# board.net
KiCad netlist of a schematic drawn in EAGLE
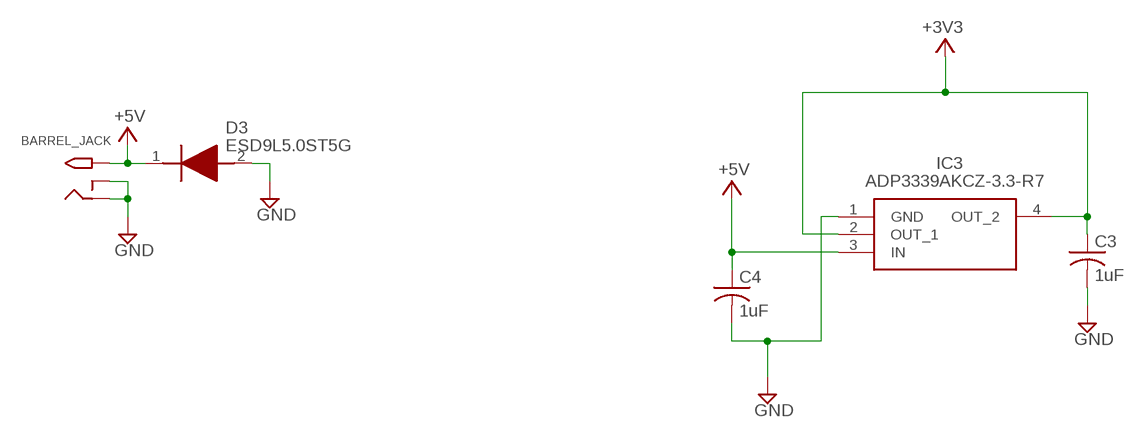
[diagram p0: schematic, sheet 1]
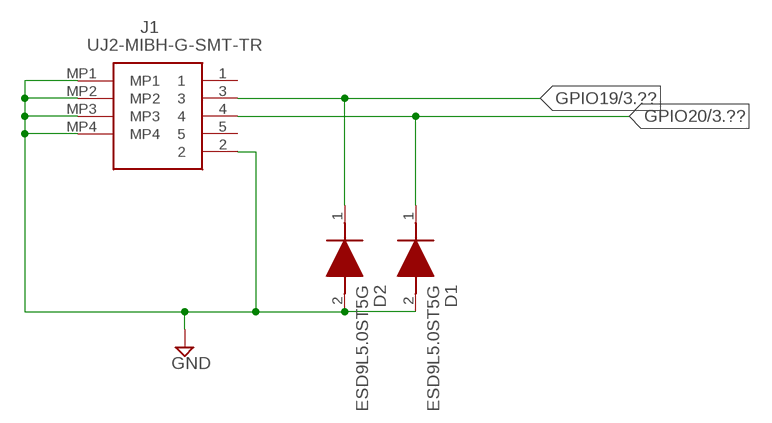
[diagram p1: schematic, sheet 2]
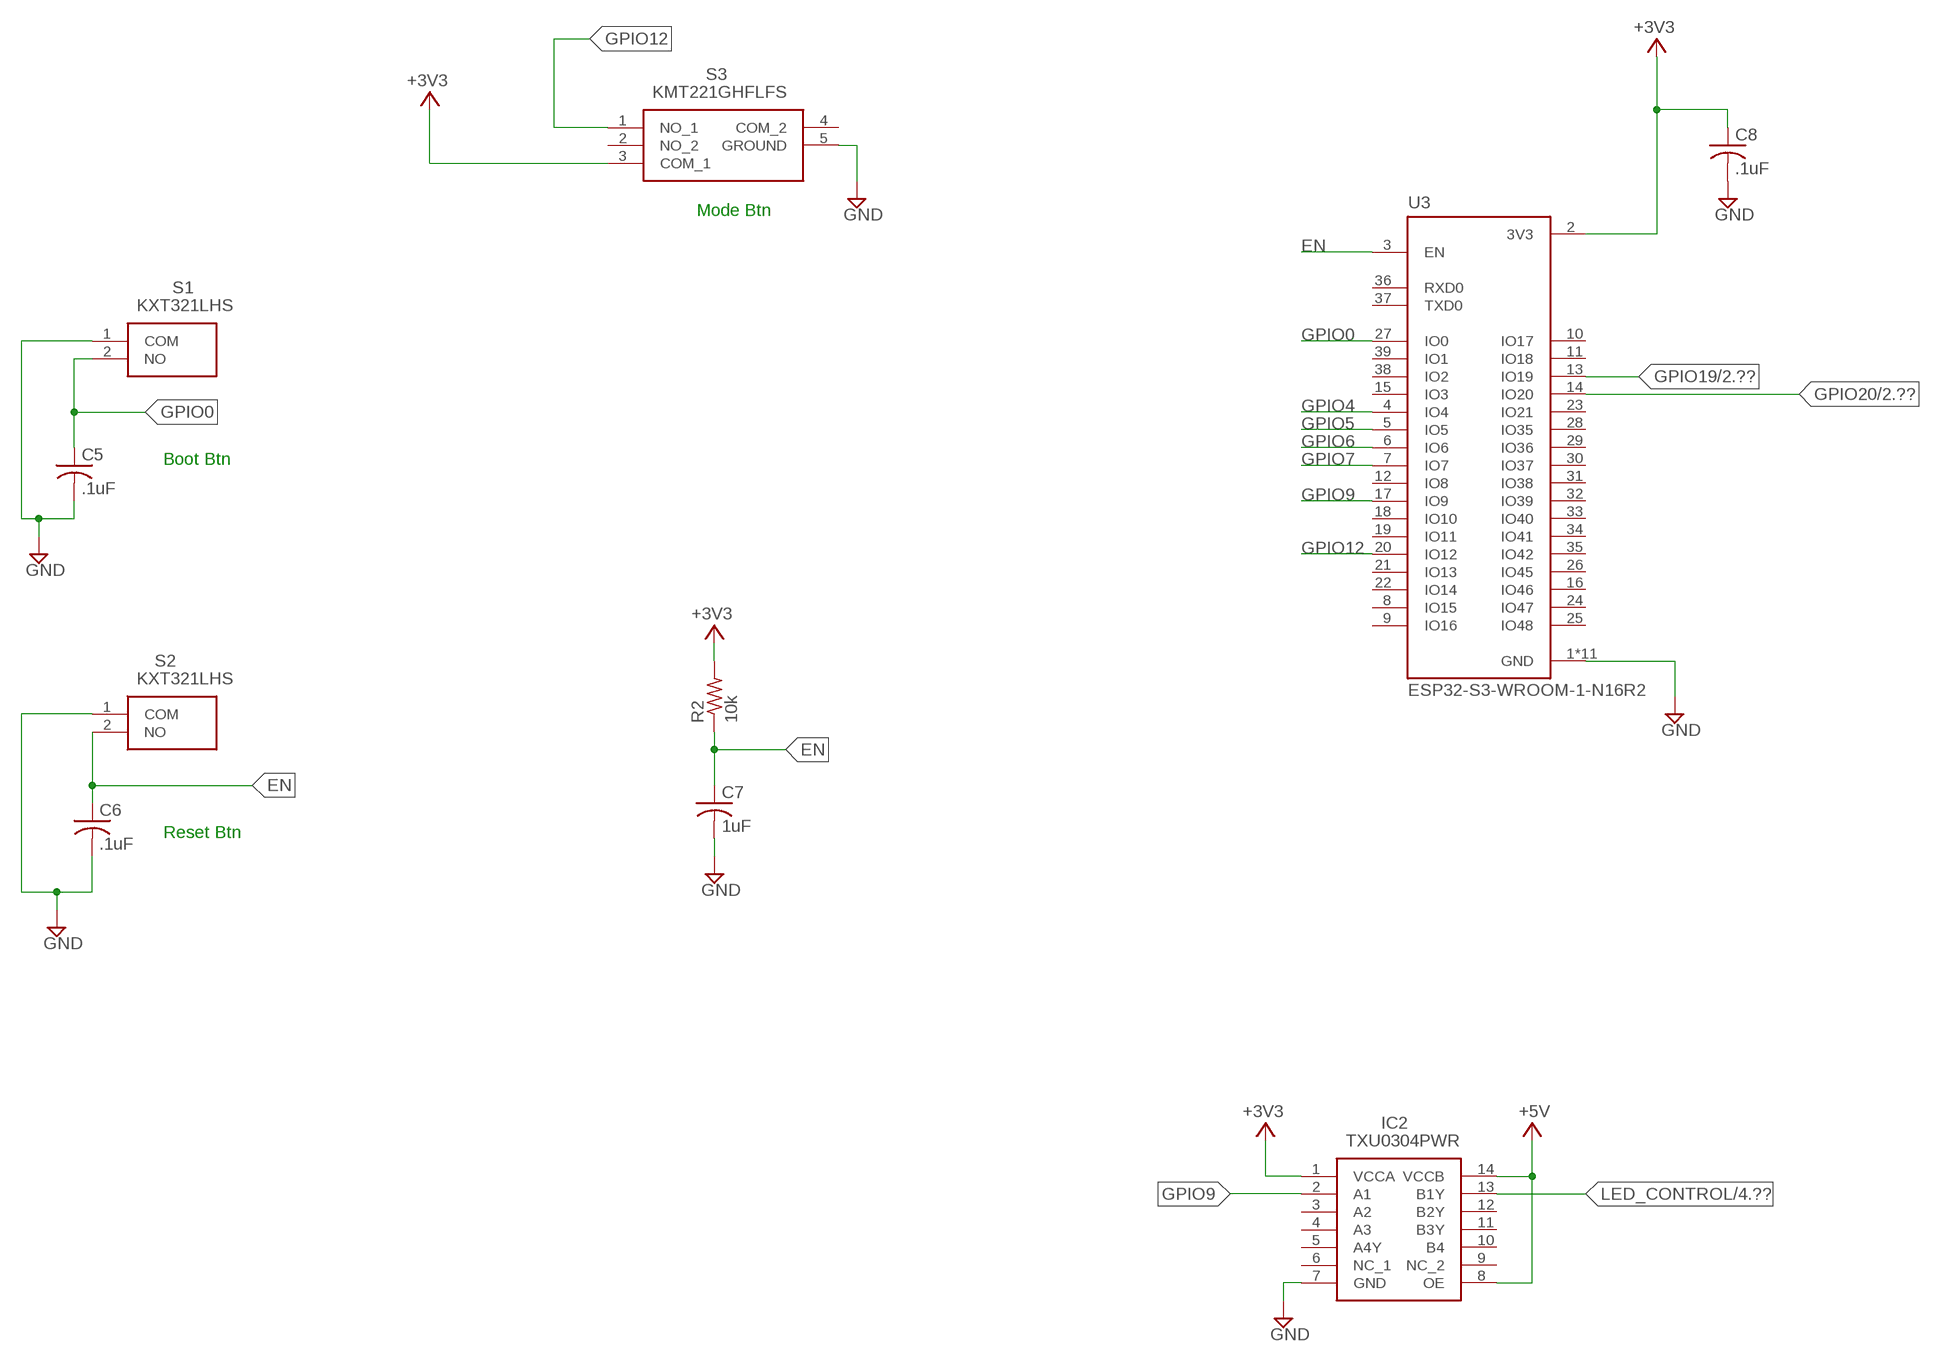
[diagram p2: schematic, sheet 3]
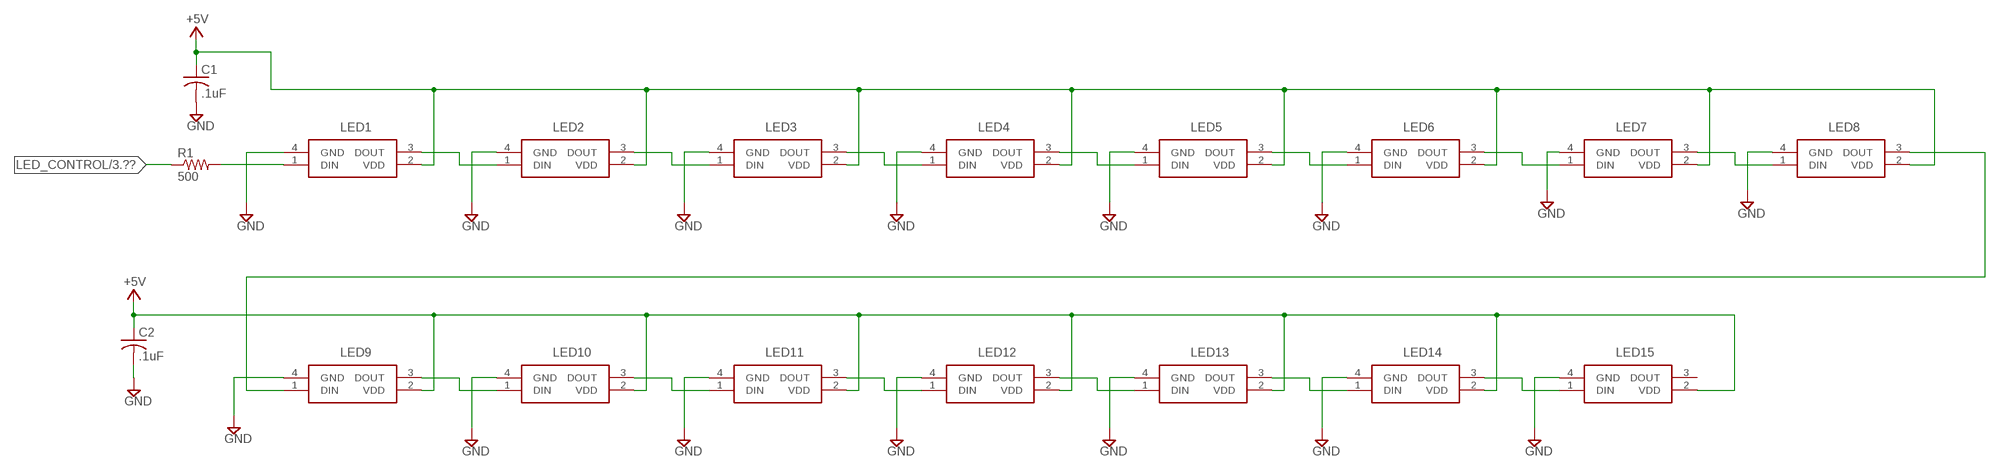
[diagram p3: schematic, sheet 4]
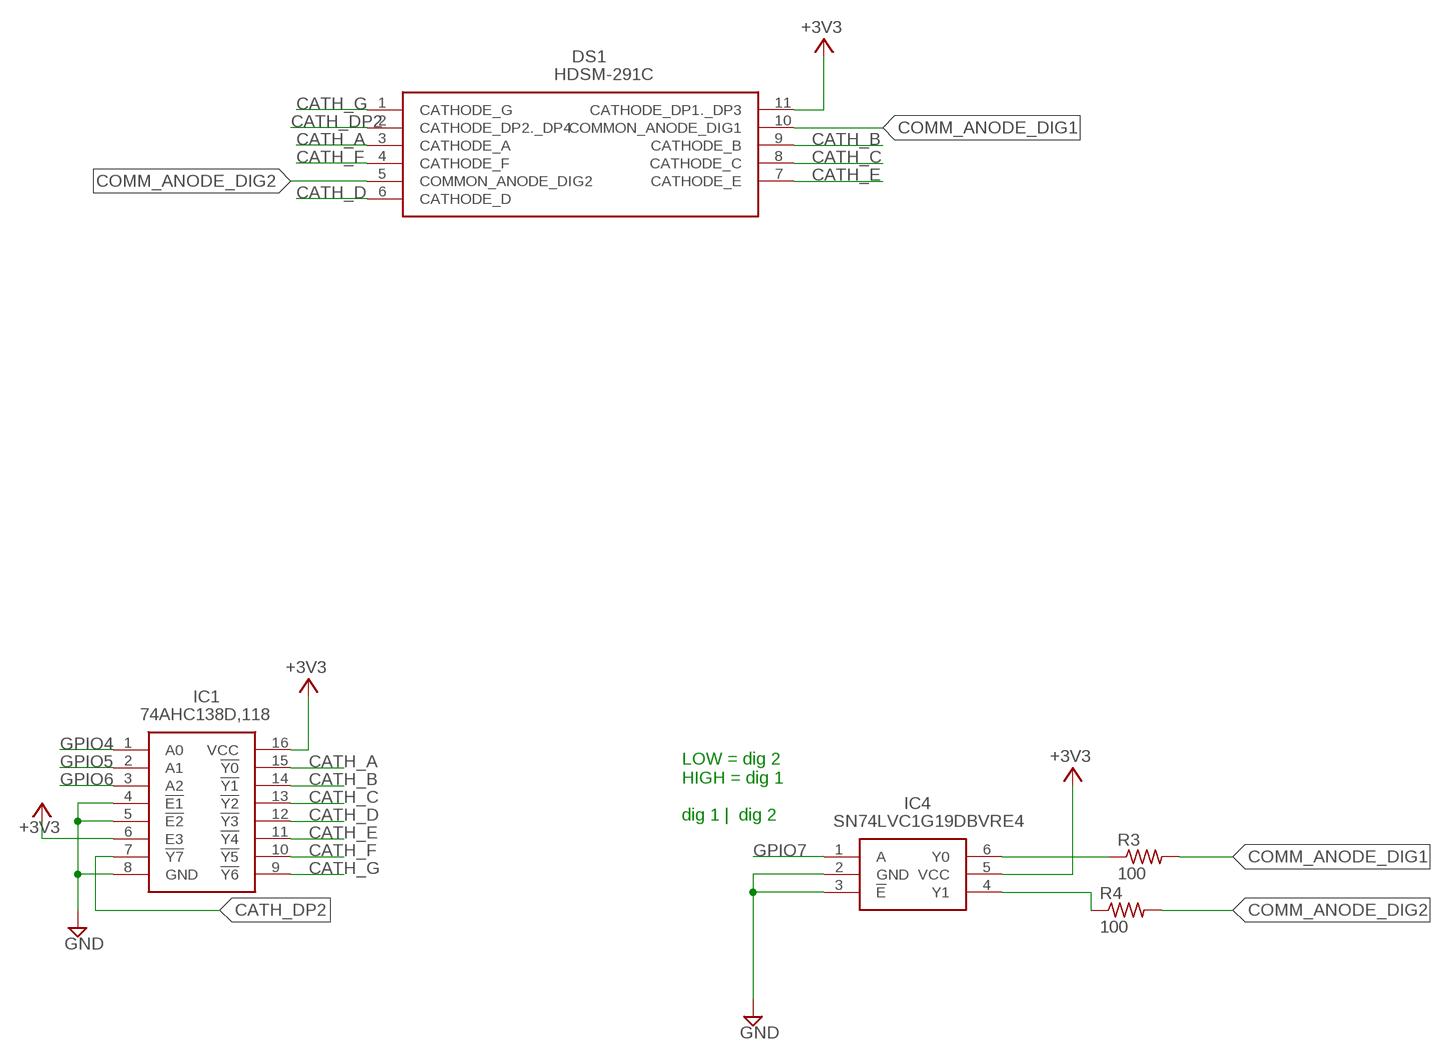
[diagram p4: schematic, sheet 5]

(export (version "E")
  (design (tool "Eeschema 10.0.6"))
  (components
    (comp (ref "C5")
      (value ".1uF")
      (footprint "eagle-import:C0402")
      (libsource (lib "eagle-import") (part "C-USC0402"))
    )
    (comp (ref "C6")
      (value ".1uF")
      (footprint "eagle-import:C0402")
      (libsource (lib "eagle-import") (part "C-USC0402"))
    )
    (comp (ref "C7")
      (value "1uF")
      (footprint "eagle-import:C0402")
      (libsource (lib "eagle-import") (part "C-USC0402"))
    )
    (comp (ref "C8")
      (value ".1uF")
      (footprint "eagle-import:C0402")
      (libsource (lib "eagle-import") (part "C-USC0402"))
    )
    (comp (ref "IC2")
      (value "TXU0304PWR")
      (footprint "eagle-import:SOP65P640X120-14N")
      (fields (field (name "MOUSER_PART_NUMBER") "595-TXU0304PWR"))
      (libsource (lib "eagle-import") (part "TXU0304PWR"))
    )
    (comp (ref "R2")
      (value "10k")
      (footprint "eagle-import:R0402")
      (libsource (lib "eagle-import") (part "R-US_R0402"))
    )
    (comp (ref "S1")
      (value "KXT321LHS")
      (footprint "eagle-import:KXT321LHS")
      (fields (field (name "MOUSER_PART_NUMBER") "611-KXT321LHS"))
      (libsource (lib "eagle-import") (part "KXT321LHS"))
    )
    (comp (ref "S2")
      (value "KXT321LHS")
      (footprint "eagle-import:KXT321LHS")
      (fields (field (name "MOUSER_PART_NUMBER") "611-KXT321LHS"))
      (libsource (lib "eagle-import") (part "KXT321LHS"))
    )
    (comp (ref "S3")
      (value "KMT221GHFLFS")
      (footprint "eagle-import:KMT221GHFLFS")
      (fields (field (name "MOUSER_PART_NUMBER") "611-KMT221GHFLFS"))
      (libsource (lib "eagle-import") (part "KMT221GHFLFS"))
    )
    (comp (ref "U3")
      (value "ESP32-S3-WROOM-1-N16R2")
      (footprint "eagle-import:XCVR_ESP32-S3-WROOM-1-N16R2")
      (fields (field (name "MF") "Espressif Systems"))
      (libsource (lib "eagle-import") (part "ESP32-S3-WROOM-1-N16R2"))
    )
    (comp (ref "D1")
      (value "ESD9L5.0ST5G")
      (footprint "eagle-import:SODFL1006X40N")
      (fields (field (name "MOUSER_PART_NUMBER") "863-ESD9L5.0ST5G"))
      (libsource (lib "eagle-import") (part "ESD9L5.0ST5G"))
    )
    (comp (ref "D2")
      (value "ESD9L5.0ST5G")
      (footprint "eagle-import:SODFL1006X40N")
      (fields (field (name "MOUSER_PART_NUMBER") "863-ESD9L5.0ST5G"))
      (libsource (lib "eagle-import") (part "ESD9L5.0ST5G"))
    )
    (comp (ref "J1")
      (value "UJ2-MIBH-G-SMT-TR")
      (footprint "eagle-import:UJ2MIBHGSMTTR")
      (fields (field (name "MOUSER_PART_NUMBER") "490-UJ2-MIBH-G-SMTTR"))
      (libsource (lib "eagle-import") (part "UJ2-MIBH-G-SMT-TR"))
    )
    (comp (ref "DS1")
      (value "HDSM-291C")
      (footprint "eagle-import:HDSM291C")
      (fields (field (name "MOUSER_PART_NUMBER") "630-HDSM-291C"))
      (libsource (lib "eagle-import") (part "HDSM-291C"))
    )
    (comp (ref "IC1")
      (value "74AHC138D,118")
      (footprint "eagle-import:SOIC127P600X175-16N")
      (fields (field (name "MOUSER_PART_NUMBER") "771-74AHC138D-T"))
      (libsource (lib "eagle-import") (part "74AHC138D,118"))
    )
    (comp (ref "IC4")
      (value "SN74LVC1G19DBVRE4")
      (footprint "eagle-import:SOT95P280X145-6N")
      (fields (field (name "MOUSER_PART_NUMBER") "595-74LVC1G19DBVRE4"))
      (libsource (lib "eagle-import") (part "SN74LVC1G19DBVRE4"))
    )
    (comp (ref "R3")
      (value "100")
      (footprint "eagle-import:R0402")
      (libsource (lib "eagle-import") (part "R-US_R0402"))
    )
    (comp (ref "R4")
      (value "100")
      (footprint "eagle-import:R0402")
      (libsource (lib "eagle-import") (part "R-US_R0402"))
    )
    (comp (ref "BARREL_JACK")
      (value "2.1MMJACKTHM")
      (footprint "eagle-import:PJ-102A")
      (libsource (lib "eagle-import") (part "2.1MMJACKTHM"))
    )
    (comp (ref "C3")
      (value "1uF")
      (footprint "eagle-import:C0402")
      (libsource (lib "eagle-import") (part "C-USC0402"))
    )
    (comp (ref "C4")
      (value "1uF")
      (footprint "eagle-import:C0402")
      (libsource (lib "eagle-import") (part "C-USC0402"))
    )
    (comp (ref "D3")
      (value "ESD9L5.0ST5G")
      (footprint "eagle-import:SODFL1006X40N")
      (fields (field (name "MOUSER_PART_NUMBER") "863-ESD9L5.0ST5G"))
      (libsource (lib "eagle-import") (part "ESD9L5.0ST5G"))
    )
    (comp (ref "IC3")
      (value "ADP3339AKCZ-3.3-R7")
      (footprint "eagle-import:SOT230P700X180-4N")
      (fields (field (name "MOUSER_PART_NUMBER") "584-ADP3339AKCZ3.3R7"))
      (libsource (lib "eagle-import") (part "ADP3339AKCZ-3.3-R7"))
    )
    (comp (ref "C1")
      (value ".1uF")
      (footprint "eagle-import:C0402")
      (libsource (lib "eagle-import") (part "C-USC0402"))
    )
    (comp (ref "C2")
      (value ".1uF")
      (footprint "eagle-import:C0402")
      (libsource (lib "eagle-import") (part "C-USC0402"))
    )
    (comp (ref "LED1")
      (value "4492__SK6805-EC_15_")
      (footprint "eagle-import:4492SK6805EC15")
      (fields (field (name "MANUFACTURER_PART_NUMBER") "4492 (SK6805-EC 15)"))
      (libsource (lib "eagle-import") (part "4492__SK6805-EC_15_"))
    )
    (comp (ref "LED2")
      (value "4492__SK6805-EC_15_")
      (footprint "eagle-import:4492SK6805EC15")
      (fields (field (name "MANUFACTURER_PART_NUMBER") "4492 (SK6805-EC 15)"))
      (libsource (lib "eagle-import") (part "4492__SK6805-EC_15_"))
    )
    (comp (ref "LED3")
      (value "4492__SK6805-EC_15_")
      (footprint "eagle-import:4492SK6805EC15")
      (fields (field (name "MANUFACTURER_PART_NUMBER") "4492 (SK6805-EC 15)"))
      (libsource (lib "eagle-import") (part "4492__SK6805-EC_15_"))
    )
    (comp (ref "LED4")
      (value "4492__SK6805-EC_15_")
      (footprint "eagle-import:4492SK6805EC15")
      (fields (field (name "MANUFACTURER_PART_NUMBER") "4492 (SK6805-EC 15)"))
      (libsource (lib "eagle-import") (part "4492__SK6805-EC_15_"))
    )
    (comp (ref "LED5")
      (value "4492__SK6805-EC_15_")
      (footprint "eagle-import:4492SK6805EC15")
      (fields (field (name "MANUFACTURER_PART_NUMBER") "4492 (SK6805-EC 15)"))
      (libsource (lib "eagle-import") (part "4492__SK6805-EC_15_"))
    )
    (comp (ref "LED6")
      (value "4492__SK6805-EC_15_")
      (footprint "eagle-import:4492SK6805EC15")
      (fields (field (name "MANUFACTURER_PART_NUMBER") "4492 (SK6805-EC 15)"))
      (libsource (lib "eagle-import") (part "4492__SK6805-EC_15_"))
    )
    (comp (ref "LED7")
      (value "4492__SK6805-EC_15_")
      (footprint "eagle-import:4492SK6805EC15")
      (fields (field (name "MANUFACTURER_PART_NUMBER") "4492 (SK6805-EC 15)"))
      (libsource (lib "eagle-import") (part "4492__SK6805-EC_15_"))
    )
    (comp (ref "LED8")
      (value "4492__SK6805-EC_15_")
      (footprint "eagle-import:4492SK6805EC15")
      (fields (field (name "MANUFACTURER_PART_NUMBER") "4492 (SK6805-EC 15)"))
      (libsource (lib "eagle-import") (part "4492__SK6805-EC_15_"))
    )
    (comp (ref "LED9")
      (value "4492__SK6805-EC_15_")
      (footprint "eagle-import:4492SK6805EC15")
      (fields (field (name "MANUFACTURER_PART_NUMBER") "4492 (SK6805-EC 15)"))
      (libsource (lib "eagle-import") (part "4492__SK6805-EC_15_"))
    )
    (comp (ref "LED10")
      (value "4492__SK6805-EC_15_")
      (footprint "eagle-import:4492SK6805EC15")
      (fields (field (name "MANUFACTURER_PART_NUMBER") "4492 (SK6805-EC 15)"))
      (libsource (lib "eagle-import") (part "4492__SK6805-EC_15_"))
    )
    (comp (ref "LED11")
      (value "4492__SK6805-EC_15_")
      (footprint "eagle-import:4492SK6805EC15")
      (fields (field (name "MANUFACTURER_PART_NUMBER") "4492 (SK6805-EC 15)"))
      (libsource (lib "eagle-import") (part "4492__SK6805-EC_15_"))
    )
    (comp (ref "LED12")
      (value "4492__SK6805-EC_15_")
      (footprint "eagle-import:4492SK6805EC15")
      (fields (field (name "MANUFACTURER_PART_NUMBER") "4492 (SK6805-EC 15)"))
      (libsource (lib "eagle-import") (part "4492__SK6805-EC_15_"))
    )
    (comp (ref "LED13")
      (value "4492__SK6805-EC_15_")
      (footprint "eagle-import:4492SK6805EC15")
      (fields (field (name "MANUFACTURER_PART_NUMBER") "4492 (SK6805-EC 15)"))
      (libsource (lib "eagle-import") (part "4492__SK6805-EC_15_"))
    )
    (comp (ref "LED14")
      (value "4492__SK6805-EC_15_")
      (footprint "eagle-import:4492SK6805EC15")
      (fields (field (name "MANUFACTURER_PART_NUMBER") "4492 (SK6805-EC 15)"))
      (libsource (lib "eagle-import") (part "4492__SK6805-EC_15_"))
    )
    (comp (ref "LED15")
      (value "4492__SK6805-EC_15_")
      (footprint "eagle-import:4492SK6805EC15")
      (fields (field (name "MANUFACTURER_PART_NUMBER") "4492 (SK6805-EC 15)"))
      (libsource (lib "eagle-import") (part "4492__SK6805-EC_15_"))
    )
    (comp (ref "R1")
      (value "500")
      (footprint "eagle-import:R0402")
      (libsource (lib "eagle-import") (part "R-US_R0402"))
    )
  )
  (nets
    (net (code "1") (name "+3V3") (class "Default")
      (node (ref "C3") (pin "1") (pinfunction "1_1") (pintype "passive"))
      (node (ref "C8") (pin "1") (pinfunction "1_1") (pintype "passive"))
      (node (ref "DS1") (pin "11") (pinfunction "CATHODE_DP1._DP3_11") (pintype "bidirectional"))
      (node (ref "IC1") (pin "16") (pinfunction "VCC_16") (pintype "bidirectional"))
      (node (ref "IC1") (pin "6") (pinfunction "E3_6") (pintype "bidirectional"))
      (node (ref "IC2") (pin "1") (pinfunction "VCCA_1") (pintype "bidirectional"))
      (node (ref "IC3") (pin "2") (pinfunction "OUT_1_2") (pintype "bidirectional"))
      (node (ref "IC3") (pin "4") (pinfunction "OUT_2_4") (pintype "bidirectional"))
      (node (ref "IC4") (pin "5") (pinfunction "VCC_5") (pintype "bidirectional"))
      (node (ref "R2") (pin "2") (pinfunction "2_2") (pintype "passive"))
      (node (ref "S3") (pin "3") (pinfunction "COM_1_3") (pintype "bidirectional"))
      (node (ref "U3") (pin "2") (pinfunction "3V3_2") (pintype "power_in"))
    )
    (net (code "2") (name "+5V") (class "Default")
      (node (ref "BARREL_JACK") (pin "TIP") (pinfunction "TIP_TIP") (pintype "bidirectional"))
      (node (ref "C1") (pin "1") (pinfunction "1_1") (pintype "passive"))
      (node (ref "C2") (pin "1") (pinfunction "1_1") (pintype "passive"))
      (node (ref "C4") (pin "1") (pinfunction "1_1") (pintype "passive"))
      (node (ref "D3") (pin "1") (pinfunction "K_1") (pintype "bidirectional"))
      (node (ref "IC2") (pin "14") (pinfunction "VCCB_14") (pintype "bidirectional"))
      (node (ref "IC2") (pin "8") (pinfunction "OE_8") (pintype "bidirectional"))
      (node (ref "IC3") (pin "3") (pinfunction "IN_3") (pintype "bidirectional"))
      (node (ref "LED1") (pin "2") (pinfunction "VDD_2") (pintype "bidirectional"))
      (node (ref "LED10") (pin "2") (pinfunction "VDD_2") (pintype "bidirectional"))
      (node (ref "LED11") (pin "2") (pinfunction "VDD_2") (pintype "bidirectional"))
      (node (ref "LED12") (pin "2") (pinfunction "VDD_2") (pintype "bidirectional"))
      (node (ref "LED13") (pin "2") (pinfunction "VDD_2") (pintype "bidirectional"))
      (node (ref "LED14") (pin "2") (pinfunction "VDD_2") (pintype "bidirectional"))
      (node (ref "LED15") (pin "2") (pinfunction "VDD_2") (pintype "bidirectional"))
      (node (ref "LED2") (pin "2") (pinfunction "VDD_2") (pintype "bidirectional"))
      (node (ref "LED3") (pin "2") (pinfunction "VDD_2") (pintype "bidirectional"))
      (node (ref "LED4") (pin "2") (pinfunction "VDD_2") (pintype "bidirectional"))
      (node (ref "LED5") (pin "2") (pinfunction "VDD_2") (pintype "bidirectional"))
      (node (ref "LED6") (pin "2") (pinfunction "VDD_2") (pintype "bidirectional"))
      (node (ref "LED7") (pin "2") (pinfunction "VDD_2") (pintype "bidirectional"))
      (node (ref "LED8") (pin "2") (pinfunction "VDD_2") (pintype "bidirectional"))
      (node (ref "LED9") (pin "2") (pinfunction "VDD_2") (pintype "bidirectional"))
    )
    (net (code "3") (name "CATH_A") (class "Default")
      (node (ref "DS1") (pin "3") (pinfunction "CATHODE_A_3") (pintype "bidirectional"))
      (node (ref "IC1") (pin "15") (pinfunction "~{Y0}_15") (pintype "bidirectional"))
    )
    (net (code "4") (name "CATH_B") (class "Default")
      (node (ref "DS1") (pin "9") (pinfunction "CATHODE_B_9") (pintype "bidirectional"))
      (node (ref "IC1") (pin "14") (pinfunction "~{Y1}_14") (pintype "bidirectional"))
    )
    (net (code "5") (name "CATH_C") (class "Default")
      (node (ref "DS1") (pin "8") (pinfunction "CATHODE_C_8") (pintype "bidirectional"))
      (node (ref "IC1") (pin "13") (pinfunction "~{Y2}_13") (pintype "bidirectional"))
    )
    (net (code "6") (name "CATH_D") (class "Default")
      (node (ref "DS1") (pin "6") (pinfunction "CATHODE_D_6") (pintype "bidirectional"))
      (node (ref "IC1") (pin "12") (pinfunction "~{Y3}_12") (pintype "bidirectional"))
    )
    (net (code "7") (name "CATH_DP2") (class "Default")
      (node (ref "DS1") (pin "2") (pinfunction "CATHODE_DP2._DP4_2") (pintype "bidirectional"))
      (node (ref "IC1") (pin "7") (pinfunction "~{Y7}_7") (pintype "bidirectional"))
    )
    (net (code "8") (name "CATH_E") (class "Default")
      (node (ref "DS1") (pin "7") (pinfunction "CATHODE_E_7") (pintype "bidirectional"))
      (node (ref "IC1") (pin "11") (pinfunction "~{Y4}_11") (pintype "bidirectional"))
    )
    (net (code "9") (name "CATH_F") (class "Default")
      (node (ref "DS1") (pin "4") (pinfunction "CATHODE_F_4") (pintype "bidirectional"))
      (node (ref "IC1") (pin "10") (pinfunction "~{Y5}_10") (pintype "bidirectional"))
    )
    (net (code "10") (name "CATH_G") (class "Default")
      (node (ref "DS1") (pin "1") (pinfunction "CATHODE_G_1") (pintype "bidirectional"))
      (node (ref "IC1") (pin "9") (pinfunction "~{Y6}_9") (pintype "bidirectional"))
    )
    (net (code "11") (name "COMM_ANODE_DIG1") (class "Default")
      (node (ref "DS1") (pin "10") (pinfunction "COMMON_ANODE_DIG1_10") (pintype "bidirectional"))
      (node (ref "R3") (pin "2") (pinfunction "2_2") (pintype "passive"))
    )
    (net (code "12") (name "COMM_ANODE_DIG2") (class "Default")
      (node (ref "DS1") (pin "5") (pinfunction "COMMON_ANODE_DIG2_5") (pintype "bidirectional"))
      (node (ref "R4") (pin "2") (pinfunction "2_2") (pintype "passive"))
    )
    (net (code "13") (name "EN") (class "Default")
      (node (ref "C6") (pin "1") (pinfunction "1_1") (pintype "passive"))
      (node (ref "C7") (pin "1") (pinfunction "1_1") (pintype "passive"))
      (node (ref "R2") (pin "1") (pinfunction "1_1") (pintype "passive"))
      (node (ref "S2") (pin "2") (pinfunction "NO_2") (pintype "bidirectional"))
      (node (ref "U3") (pin "3") (pinfunction "EN_3") (pintype "input"))
    )
    (net (code "14") (name "GND") (class "Default")
      (node (ref "BARREL_JACK") (pin "RING") (pinfunction "RING_RING") (pintype "bidirectional"))
      (node (ref "BARREL_JACK") (pin "RING_SW") (pinfunction "RING_SW_RING_SW") (pintype "bidirectional"))
      (node (ref "C1") (pin "2") (pinfunction "2_2") (pintype "passive"))
      (node (ref "C2") (pin "2") (pinfunction "2_2") (pintype "passive"))
      (node (ref "C3") (pin "2") (pinfunction "2_2") (pintype "passive"))
      (node (ref "C4") (pin "2") (pinfunction "2_2") (pintype "passive"))
      (node (ref "C5") (pin "2") (pinfunction "2_2") (pintype "passive"))
      (node (ref "C6") (pin "2") (pinfunction "2_2") (pintype "passive"))
      (node (ref "C7") (pin "2") (pinfunction "2_2") (pintype "passive"))
      (node (ref "C8") (pin "2") (pinfunction "2_2") (pintype "passive"))
      (node (ref "D1") (pin "2") (pinfunction "A_2") (pintype "bidirectional"))
      (node (ref "D2") (pin "2") (pinfunction "A_2") (pintype "bidirectional"))
      (node (ref "D3") (pin "2") (pinfunction "A_2") (pintype "bidirectional"))
      (node (ref "IC1") (pin "4") (pinfunction "~{E1}_4") (pintype "bidirectional"))
      (node (ref "IC1") (pin "5") (pinfunction "~{E2}_5") (pintype "bidirectional"))
      (node (ref "IC1") (pin "8") (pinfunction "GND_8") (pintype "bidirectional"))
      (node (ref "IC2") (pin "7") (pinfunction "GND_7") (pintype "bidirectional"))
      (node (ref "IC3") (pin "1") (pinfunction "GND_1") (pintype "bidirectional"))
      (node (ref "IC4") (pin "2") (pinfunction "GND_2") (pintype "bidirectional"))
      (node (ref "IC4") (pin "3") (pinfunction "~{E}_3") (pintype "bidirectional"))
      (node (ref "J1") (pin "2") (pinfunction "2_2") (pintype "bidirectional"))
      (node (ref "J1") (pin "MP1") (pinfunction "MP1_MP1") (pintype "bidirectional"))
      (node (ref "J1") (pin "MP2") (pinfunction "MP2_MP2") (pintype "bidirectional"))
      (node (ref "J1") (pin "MP3") (pinfunction "MP3_MP3") (pintype "bidirectional"))
      (node (ref "J1") (pin "MP4") (pinfunction "MP4_MP4") (pintype "bidirectional"))
      (node (ref "LED1") (pin "4") (pinfunction "GND_4") (pintype "bidirectional"))
      (node (ref "LED10") (pin "4") (pinfunction "GND_4") (pintype "bidirectional"))
      (node (ref "LED11") (pin "4") (pinfunction "GND_4") (pintype "bidirectional"))
      (node (ref "LED12") (pin "4") (pinfunction "GND_4") (pintype "bidirectional"))
      (node (ref "LED13") (pin "4") (pinfunction "GND_4") (pintype "bidirectional"))
      (node (ref "LED14") (pin "4") (pinfunction "GND_4") (pintype "bidirectional"))
      (node (ref "LED15") (pin "4") (pinfunction "GND_4") (pintype "bidirectional"))
      (node (ref "LED2") (pin "4") (pinfunction "GND_4") (pintype "bidirectional"))
      (node (ref "LED3") (pin "4") (pinfunction "GND_4") (pintype "bidirectional"))
      (node (ref "LED4") (pin "4") (pinfunction "GND_4") (pintype "bidirectional"))
      (node (ref "LED5") (pin "4") (pinfunction "GND_4") (pintype "bidirectional"))
      (node (ref "LED6") (pin "4") (pinfunction "GND_4") (pintype "bidirectional"))
      (node (ref "LED7") (pin "4") (pinfunction "GND_4") (pintype "bidirectional"))
      (node (ref "LED8") (pin "4") (pinfunction "GND_4") (pintype "bidirectional"))
      (node (ref "LED9") (pin "4") (pinfunction "GND_4") (pintype "bidirectional"))
      (node (ref "S1") (pin "1") (pinfunction "COM_1") (pintype "bidirectional"))
      (node (ref "S2") (pin "1") (pinfunction "COM_1") (pintype "bidirectional"))
      (node (ref "S3") (pin "5") (pinfunction "GROUND_5") (pintype "bidirectional"))
      (node (ref "U3") (pin "1") (pinfunction "GND_1") (pintype "power_in"))
      (node (ref "U3") (pin "40") (pinfunction "GND_40") (pintype "power_in"))
      (node (ref "U3") (pin "41_1") (pinfunction "GND_41_1") (pintype "power_in"))
      (node (ref "U3") (pin "41_2") (pinfunction "GND_41_2") (pintype "power_in"))
      (node (ref "U3") (pin "41_3") (pinfunction "GND_41_3") (pintype "power_in"))
      (node (ref "U3") (pin "41_4") (pinfunction "GND_41_4") (pintype "power_in"))
      (node (ref "U3") (pin "41_5") (pinfunction "GND_41_5") (pintype "power_in"))
      (node (ref "U3") (pin "41_6") (pinfunction "GND_41_6") (pintype "power_in"))
      (node (ref "U3") (pin "41_7") (pinfunction "GND_41_7") (pintype "power_in"))
      (node (ref "U3") (pin "41_8") (pinfunction "GND_41_8") (pintype "power_in"))
      (node (ref "U3") (pin "41_9") (pinfunction "GND_41_9") (pintype "power_in"))
    )
    (net (code "15") (name "GPIO0") (class "Default")
      (node (ref "C5") (pin "1") (pinfunction "1_1") (pintype "passive"))
      (node (ref "S1") (pin "2") (pinfunction "NO_2") (pintype "bidirectional"))
      (node (ref "U3") (pin "27") (pinfunction "IO0_27") (pintype "bidirectional"))
    )
    (net (code "16") (name "GPIO4") (class "Default")
      (node (ref "IC1") (pin "1") (pinfunction "A0_1") (pintype "bidirectional"))
      (node (ref "U3") (pin "4") (pinfunction "IO4_4") (pintype "bidirectional"))
    )
    (net (code "17") (name "GPIO5") (class "Default")
      (node (ref "IC1") (pin "2") (pinfunction "A1_2") (pintype "bidirectional"))
      (node (ref "U3") (pin "5") (pinfunction "IO5_5") (pintype "bidirectional"))
    )
    (net (code "18") (name "GPIO6") (class "Default")
      (node (ref "IC1") (pin "3") (pinfunction "A2_3") (pintype "bidirectional"))
      (node (ref "U3") (pin "6") (pinfunction "IO6_6") (pintype "bidirectional"))
    )
    (net (code "19") (name "GPIO7") (class "Default")
      (node (ref "IC4") (pin "1") (pinfunction "A_1") (pintype "bidirectional"))
      (node (ref "U3") (pin "7") (pinfunction "IO7_7") (pintype "bidirectional"))
    )
    (net (code "20") (name "GPIO9") (class "Default")
      (node (ref "IC2") (pin "2") (pinfunction "A1_2") (pintype "bidirectional"))
      (node (ref "U3") (pin "17") (pinfunction "IO9_17") (pintype "bidirectional"))
    )
    (net (code "21") (name "GPIO12") (class "Default")
      (node (ref "S3") (pin "1") (pinfunction "NO_1_1") (pintype "bidirectional"))
      (node (ref "U3") (pin "20") (pinfunction "IO12_20") (pintype "bidirectional"))
    )
    (net (code "22") (name "GPIO19") (class "Default")
      (node (ref "D2") (pin "1") (pinfunction "K_1") (pintype "bidirectional"))
      (node (ref "J1") (pin "3") (pinfunction "3_3") (pintype "bidirectional"))
      (node (ref "U3") (pin "13") (pinfunction "IO19_13") (pintype "bidirectional"))
    )
    (net (code "23") (name "GPIO20") (class "Default")
      (node (ref "D1") (pin "1") (pinfunction "K_1") (pintype "bidirectional"))
      (node (ref "J1") (pin "4") (pinfunction "4_4") (pintype "bidirectional"))
      (node (ref "U3") (pin "14") (pinfunction "IO20_14") (pintype "bidirectional"))
    )
    (net (code "24") (name "LED_CONTROL") (class "Default")
      (node (ref "IC2") (pin "13") (pinfunction "B1Y_13") (pintype "bidirectional"))
      (node (ref "R1") (pin "1") (pinfunction "1_1") (pintype "passive"))
    )
    (net (code "25") (name "Net-(IC4-Y0)") (class "Default")
      (node (ref "IC4") (pin "6") (pinfunction "Y0_6") (pintype "bidirectional"))
      (node (ref "R3") (pin "1") (pinfunction "1_1") (pintype "passive"))
    )
    (net (code "26") (name "Net-(IC4-Y1)") (class "Default")
      (node (ref "IC4") (pin "4") (pinfunction "Y1_4") (pintype "bidirectional"))
      (node (ref "R4") (pin "1") (pinfunction "1_1") (pintype "passive"))
    )
    (net (code "27") (name "Net-(LED1-DIN)") (class "Default")
      (node (ref "LED1") (pin "1") (pinfunction "DIN_1") (pintype "bidirectional"))
      (node (ref "R1") (pin "2") (pinfunction "2_2") (pintype "passive"))
    )
    (net (code "28") (name "Net-(LED1-DOUT)") (class "Default")
      (node (ref "LED1") (pin "3") (pinfunction "DOUT_3") (pintype "bidirectional"))
      (node (ref "LED2") (pin "1") (pinfunction "DIN_1") (pintype "bidirectional"))
    )
    (net (code "29") (name "Net-(LED2-DOUT)") (class "Default")
      (node (ref "LED2") (pin "3") (pinfunction "DOUT_3") (pintype "bidirectional"))
      (node (ref "LED3") (pin "1") (pinfunction "DIN_1") (pintype "bidirectional"))
    )
    (net (code "30") (name "Net-(LED3-DOUT)") (class "Default")
      (node (ref "LED3") (pin "3") (pinfunction "DOUT_3") (pintype "bidirectional"))
      (node (ref "LED4") (pin "1") (pinfunction "DIN_1") (pintype "bidirectional"))
    )
    (net (code "31") (name "Net-(LED4-DOUT)") (class "Default")
      (node (ref "LED4") (pin "3") (pinfunction "DOUT_3") (pintype "bidirectional"))
      (node (ref "LED5") (pin "1") (pinfunction "DIN_1") (pintype "bidirectional"))
    )
    (net (code "32") (name "Net-(LED5-DOUT)") (class "Default")
      (node (ref "LED5") (pin "3") (pinfunction "DOUT_3") (pintype "bidirectional"))
      (node (ref "LED6") (pin "1") (pinfunction "DIN_1") (pintype "bidirectional"))
    )
    (net (code "33") (name "Net-(LED6-DOUT)") (class "Default")
      (node (ref "LED6") (pin "3") (pinfunction "DOUT_3") (pintype "bidirectional"))
      (node (ref "LED7") (pin "1") (pinfunction "DIN_1") (pintype "bidirectional"))
    )
    (net (code "34") (name "Net-(LED7-DOUT)") (class "Default")
      (node (ref "LED7") (pin "3") (pinfunction "DOUT_3") (pintype "bidirectional"))
      (node (ref "LED8") (pin "1") (pinfunction "DIN_1") (pintype "bidirectional"))
    )
    (net (code "35") (name "Net-(LED8-DOUT)") (class "Default")
      (node (ref "LED8") (pin "3") (pinfunction "DOUT_3") (pintype "bidirectional"))
      (node (ref "LED9") (pin "1") (pinfunction "DIN_1") (pintype "bidirectional"))
    )
    (net (code "36") (name "Net-(LED10-DIN)") (class "Default")
      (node (ref "LED10") (pin "1") (pinfunction "DIN_1") (pintype "bidirectional"))
      (node (ref "LED9") (pin "3") (pinfunction "DOUT_3") (pintype "bidirectional"))
    )
    (net (code "37") (name "Net-(LED10-DOUT)") (class "Default")
      (node (ref "LED10") (pin "3") (pinfunction "DOUT_3") (pintype "bidirectional"))
      (node (ref "LED11") (pin "1") (pinfunction "DIN_1") (pintype "bidirectional"))
    )
    (net (code "38") (name "Net-(LED11-DOUT)") (class "Default")
      (node (ref "LED11") (pin "3") (pinfunction "DOUT_3") (pintype "bidirectional"))
      (node (ref "LED12") (pin "1") (pinfunction "DIN_1") (pintype "bidirectional"))
    )
    (net (code "39") (name "Net-(LED12-DOUT)") (class "Default")
      (node (ref "LED12") (pin "3") (pinfunction "DOUT_3") (pintype "bidirectional"))
      (node (ref "LED13") (pin "1") (pinfunction "DIN_1") (pintype "bidirectional"))
    )
    (net (code "40") (name "Net-(LED13-DOUT)") (class "Default")
      (node (ref "LED13") (pin "3") (pinfunction "DOUT_3") (pintype "bidirectional"))
      (node (ref "LED14") (pin "1") (pinfunction "DIN_1") (pintype "bidirectional"))
    )
    (net (code "41") (name "Net-(LED14-DOUT)") (class "Default")
      (node (ref "LED14") (pin "3") (pinfunction "DOUT_3") (pintype "bidirectional"))
      (node (ref "LED15") (pin "1") (pinfunction "DIN_1") (pintype "bidirectional"))
    )
    (net (code "42") (name "unconnected-(IC2-A2-Pad3)") (class "Default")
      (node (ref "IC2") (pin "3") (pinfunction "A2_3") (pintype "bidirectional"))
    )
    (net (code "43") (name "unconnected-(IC2-A3-Pad4)") (class "Default")
      (node (ref "IC2") (pin "4") (pinfunction "A3_4") (pintype "bidirectional"))
    )
    (net (code "44") (name "unconnected-(IC2-A4Y-Pad5)") (class "Default")
      (node (ref "IC2") (pin "5") (pinfunction "A4Y_5") (pintype "bidirectional"))
    )
    (net (code "45") (name "unconnected-(IC2-B2Y-Pad12)") (class "Default")
      (node (ref "IC2") (pin "12") (pinfunction "B2Y_12") (pintype "bidirectional"))
    )
    (net (code "46") (name "unconnected-(IC2-B3Y-Pad11)") (class "Default")
      (node (ref "IC2") (pin "11") (pinfunction "B3Y_11") (pintype "bidirectional"))
    )
    (net (code "47") (name "unconnected-(IC2-B4-Pad10)") (class "Default")
      (node (ref "IC2") (pin "10") (pinfunction "B4_10") (pintype "bidirectional"))
    )
    (net (code "48") (name "unconnected-(IC2-NC_1-Pad6)") (class "Default")
      (node (ref "IC2") (pin "6") (pinfunction "NC_1_6") (pintype "bidirectional"))
    )
    (net (code "49") (name "unconnected-(IC2-NC_2-Pad9)") (class "Default")
      (node (ref "IC2") (pin "9") (pinfunction "NC_2_9") (pintype "bidirectional"))
    )
    (net (code "50") (name "unconnected-(J1-Pad1)") (class "Default")
      (node (ref "J1") (pin "1") (pinfunction "1_1") (pintype "bidirectional"))
    )
    (net (code "51") (name "unconnected-(J1-Pad5)") (class "Default")
      (node (ref "J1") (pin "5") (pinfunction "5_5") (pintype "bidirectional"))
    )
    (net (code "52") (name "unconnected-(LED15-DOUT-Pad3)") (class "Default")
      (node (ref "LED15") (pin "3") (pinfunction "DOUT_3") (pintype "bidirectional"))
    )
    (net (code "53") (name "unconnected-(S3-COM_2-Pad4)") (class "Default")
      (node (ref "S3") (pin "4") (pinfunction "COM_2_4") (pintype "bidirectional"))
    )
    (net (code "54") (name "unconnected-(S3-NO_2-Pad2)") (class "Default")
      (node (ref "S3") (pin "2") (pinfunction "NO_2_2") (pintype "bidirectional"))
    )
    (net (code "55") (name "unconnected-(U3-IO1-Pad39)") (class "Default")
      (node (ref "U3") (pin "39") (pinfunction "IO1_39") (pintype "bidirectional"))
    )
    (net (code "56") (name "unconnected-(U3-IO2-Pad38)") (class "Default")
      (node (ref "U3") (pin "38") (pinfunction "IO2_38") (pintype "bidirectional"))
    )
    (net (code "57") (name "unconnected-(U3-IO3-Pad15)") (class "Default")
      (node (ref "U3") (pin "15") (pinfunction "IO3_15") (pintype "bidirectional"))
    )
    (net (code "58") (name "unconnected-(U3-IO8-Pad12)") (class "Default")
      (node (ref "U3") (pin "12") (pinfunction "IO8_12") (pintype "bidirectional"))
    )
    (net (code "59") (name "unconnected-(U3-IO10-Pad18)") (class "Default")
      (node (ref "U3") (pin "18") (pinfunction "IO10_18") (pintype "bidirectional"))
    )
    (net (code "60") (name "unconnected-(U3-IO11-Pad19)") (class "Default")
      (node (ref "U3") (pin "19") (pinfunction "IO11_19") (pintype "bidirectional"))
    )
    (net (code "61") (name "unconnected-(U3-IO13-Pad21)") (class "Default")
      (node (ref "U3") (pin "21") (pinfunction "IO13_21") (pintype "bidirectional"))
    )
    (net (code "62") (name "unconnected-(U3-IO14-Pad22)") (class "Default")
      (node (ref "U3") (pin "22") (pinfunction "IO14_22") (pintype "bidirectional"))
    )
    (net (code "63") (name "unconnected-(U3-IO15-Pad8)") (class "Default")
      (node (ref "U3") (pin "8") (pinfunction "IO15_8") (pintype "bidirectional"))
    )
    (net (code "64") (name "unconnected-(U3-IO16-Pad9)") (class "Default")
      (node (ref "U3") (pin "9") (pinfunction "IO16_9") (pintype "bidirectional"))
    )
    (net (code "65") (name "unconnected-(U3-IO17-Pad10)") (class "Default")
      (node (ref "U3") (pin "10") (pinfunction "IO17_10") (pintype "bidirectional"))
    )
    (net (code "66") (name "unconnected-(U3-IO18-Pad11)") (class "Default")
      (node (ref "U3") (pin "11") (pinfunction "IO18_11") (pintype "bidirectional"))
    )
    (net (code "67") (name "unconnected-(U3-IO21-Pad23)") (class "Default")
      (node (ref "U3") (pin "23") (pinfunction "IO21_23") (pintype "bidirectional"))
    )
    (net (code "68") (name "unconnected-(U3-IO35-Pad28)") (class "Default")
      (node (ref "U3") (pin "28") (pinfunction "IO35_28") (pintype "bidirectional"))
    )
    (net (code "69") (name "unconnected-(U3-IO36-Pad29)") (class "Default")
      (node (ref "U3") (pin "29") (pinfunction "IO36_29") (pintype "bidirectional"))
    )
    (net (code "70") (name "unconnected-(U3-IO37-Pad30)") (class "Default")
      (node (ref "U3") (pin "30") (pinfunction "IO37_30") (pintype "bidirectional"))
    )
    (net (code "71") (name "unconnected-(U3-IO38-Pad31)") (class "Default")
      (node (ref "U3") (pin "31") (pinfunction "IO38_31") (pintype "bidirectional"))
    )
    (net (code "72") (name "unconnected-(U3-IO39-Pad32)") (class "Default")
      (node (ref "U3") (pin "32") (pinfunction "IO39_32") (pintype "bidirectional"))
    )
    (net (code "73") (name "unconnected-(U3-IO40-Pad33)") (class "Default")
      (node (ref "U3") (pin "33") (pinfunction "IO40_33") (pintype "bidirectional"))
    )
    (net (code "74") (name "unconnected-(U3-IO41-Pad34)") (class "Default")
      (node (ref "U3") (pin "34") (pinfunction "IO41_34") (pintype "bidirectional"))
    )
    (net (code "75") (name "unconnected-(U3-IO42-Pad35)") (class "Default")
      (node (ref "U3") (pin "35") (pinfunction "IO42_35") (pintype "bidirectional"))
    )
    (net (code "76") (name "unconnected-(U3-IO45-Pad26)") (class "Default")
      (node (ref "U3") (pin "26") (pinfunction "IO45_26") (pintype "bidirectional"))
    )
    (net (code "77") (name "unconnected-(U3-IO46-Pad16)") (class "Default")
      (node (ref "U3") (pin "16") (pinfunction "IO46_16") (pintype "bidirectional"))
    )
    (net (code "78") (name "unconnected-(U3-IO47-Pad24)") (class "Default")
      (node (ref "U3") (pin "24") (pinfunction "IO47_24") (pintype "bidirectional"))
    )
    (net (code "79") (name "unconnected-(U3-IO48-Pad25)") (class "Default")
      (node (ref "U3") (pin "25") (pinfunction "IO48_25") (pintype "bidirectional"))
    )
    (net (code "80") (name "unconnected-(U3-RXD0-Pad36)") (class "Default")
      (node (ref "U3") (pin "36") (pinfunction "RXD0_36") (pintype "bidirectional"))
    )
    (net (code "81") (name "unconnected-(U3-TXD0-Pad37)") (class "Default")
      (node (ref "U3") (pin "37") (pinfunction "TXD0_37") (pintype "bidirectional"))
    )
  )
)
